# coffee_machine.net
KiCad netlist of a schematic drawn in EAGLE
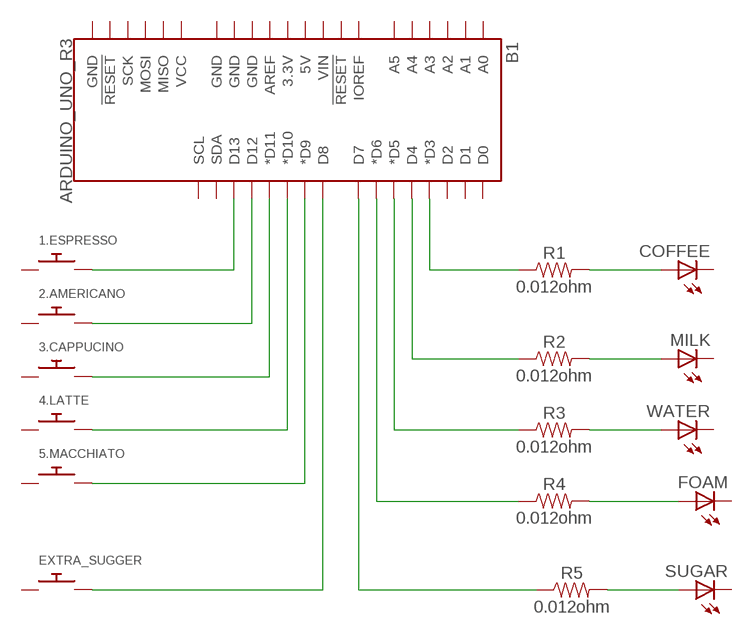
[diagram p0: schematic, sheet 1]

(export (version "E")
  (design (tool "Eeschema 10.0.6"))
  (components
    (comp (ref "1.ESPRESSO")
      (value "SWITCH_PUSHBUTTONEVQ-PE")
      (footprint "eagle-import:TACT_PANA-EVQ")
      (libsource (lib "eagle-import") (part "SWITCH_PUSHBUTTONEVQ-PE"))
    )
    (comp (ref "2.AMERICANO")
      (value "SWITCH_PUSHBUTTONEVQ-PE")
      (footprint "eagle-import:TACT_PANA-EVQ")
      (libsource (lib "eagle-import") (part "SWITCH_PUSHBUTTONEVQ-PE"))
    )
    (comp (ref "3.CAPPUCINO")
      (value "SWITCH_PUSHBUTTONEVQ-PE")
      (footprint "eagle-import:TACT_PANA-EVQ")
      (libsource (lib "eagle-import") (part "SWITCH_PUSHBUTTONEVQ-PE"))
    )
    (comp (ref "4.LATTE")
      (value "SWITCH_PUSHBUTTONEVQ-PE")
      (footprint "eagle-import:TACT_PANA-EVQ")
      (libsource (lib "eagle-import") (part "SWITCH_PUSHBUTTONEVQ-PE"))
    )
    (comp (ref "5.MACCHIATO")
      (value "SWITCH_PUSHBUTTONEVQ-PE")
      (footprint "eagle-import:TACT_PANA-EVQ")
      (libsource (lib "eagle-import") (part "SWITCH_PUSHBUTTONEVQ-PE"))
    )
    (comp (ref "B1")
      (value "ARDUINO_UNO_R3")
      (footprint "eagle-import:ARDUINO_R3")
      (libsource (lib "eagle-import") (part "ARDUINO_UNO_R3"))
    )
    (comp (ref "COFFEE")
      (value "LED3MM")
      (footprint "eagle-import:LED3MM")
      (libsource (lib "eagle-import") (part "LED3MM"))
    )
    (comp (ref "EXTRA_SUGGER")
      (value "SWITCH_PUSHBUTTONEVQ-PE")
      (footprint "eagle-import:TACT_PANA-EVQ")
      (libsource (lib "eagle-import") (part "SWITCH_PUSHBUTTONEVQ-PE"))
    )
    (comp (ref "FOAM")
      (value "LED3MM")
      (footprint "eagle-import:LED3MM")
      (libsource (lib "eagle-import") (part "LED3MM"))
    )
    (comp (ref "MILK")
      (value "LED3MM")
      (footprint "eagle-import:LED3MM")
      (libsource (lib "eagle-import") (part "LED3MM"))
    )
    (comp (ref "R1")
      (value "0.012ohm")
      (footprint "eagle-import:0603")
      (libsource (lib "eagle-import") (part "0.012OHM0603"))
    )
    (comp (ref "R2")
      (value "0.012ohm")
      (footprint "eagle-import:0603")
      (libsource (lib "eagle-import") (part "0.012OHM0603"))
    )
    (comp (ref "R3")
      (value "0.012ohm")
      (footprint "eagle-import:0603")
      (libsource (lib "eagle-import") (part "0.012OHM0603"))
    )
    (comp (ref "R4")
      (value "0.012ohm")
      (footprint "eagle-import:0603")
      (libsource (lib "eagle-import") (part "0.012OHM0603"))
    )
    (comp (ref "R5")
      (value "0.012ohm")
      (footprint "eagle-import:0603")
      (libsource (lib "eagle-import") (part "0.012OHM0603"))
    )
    (comp (ref "SUGAR")
      (value "LED3MM")
      (footprint "eagle-import:LED3MM")
      (libsource (lib "eagle-import") (part "LED3MM"))
    )
    (comp (ref "WATER")
      (value "LED3MM")
      (footprint "eagle-import:LED3MM")
      (libsource (lib "eagle-import") (part "LED3MM"))
    )
  )
  (nets
    (net (code "1") (name "Net-(1.ESPRESSO-PadP$2)") (class "Default")
      (node (ref "1.ESPRESSO") (pin "P$2") (pinfunction "P$2_P$2") (pintype "passive"))
      (node (ref "B1") (pin "D13") (pinfunction "D13_D13") (pintype "bidirectional"))
    )
    (net (code "2") (name "Net-(2.AMERICANO-PadP$2)") (class "Default")
      (node (ref "2.AMERICANO") (pin "P$2") (pinfunction "P$2_P$2") (pintype "passive"))
      (node (ref "B1") (pin "D12") (pinfunction "D12_D12") (pintype "bidirectional"))
    )
    (net (code "3") (name "Net-(B1-*D3)") (class "Default")
      (node (ref "B1") (pin "D3") (pinfunction "*D3_D3") (pintype "bidirectional"))
      (node (ref "R1") (pin "1") (pinfunction "1_1") (pintype "passive"))
    )
    (net (code "4") (name "Net-(B1-*D5)") (class "Default")
      (node (ref "B1") (pin "D5") (pinfunction "*D5_D5") (pintype "bidirectional"))
      (node (ref "R3") (pin "1") (pinfunction "1_1") (pintype "passive"))
    )
    (net (code "5") (name "Net-(B1-*D6)") (class "Default")
      (node (ref "B1") (pin "D6") (pinfunction "*D6_D6") (pintype "bidirectional"))
      (node (ref "R4") (pin "1") (pinfunction "1_1") (pintype "passive"))
    )
    (net (code "6") (name "Net-(B1-*D9)") (class "Default")
      (node (ref "5.MACCHIATO") (pin "P$2") (pinfunction "P$2_P$2") (pintype "passive"))
      (node (ref "B1") (pin "D9") (pinfunction "*D9_D9") (pintype "bidirectional"))
    )
    (net (code "7") (name "Net-(B1-*D10)") (class "Default")
      (node (ref "4.LATTE") (pin "P$2") (pinfunction "P$2_P$2") (pintype "passive"))
      (node (ref "B1") (pin "D10") (pinfunction "*D10_D10") (pintype "bidirectional"))
    )
    (net (code "8") (name "Net-(B1-*D11)") (class "Default")
      (node (ref "3.CAPPUCINO") (pin "P$2") (pinfunction "P$2_P$2") (pintype "passive"))
      (node (ref "B1") (pin "D11") (pinfunction "*D11_D11") (pintype "bidirectional"))
    )
    (net (code "9") (name "Net-(B1-PadD4)") (class "Default")
      (node (ref "B1") (pin "D4") (pinfunction "D4_D4") (pintype "bidirectional"))
      (node (ref "R2") (pin "1") (pinfunction "1_1") (pintype "passive"))
    )
    (net (code "10") (name "Net-(B1-PadD7)") (class "Default")
      (node (ref "B1") (pin "D7") (pinfunction "D7_D7") (pintype "bidirectional"))
      (node (ref "R5") (pin "1") (pinfunction "1_1") (pintype "passive"))
    )
    (net (code "11") (name "Net-(B1-PadD8)") (class "Default")
      (node (ref "B1") (pin "D8") (pinfunction "D8_D8") (pintype "bidirectional"))
      (node (ref "EXTRA_SUGGER") (pin "P$2") (pinfunction "P$2_P$2") (pintype "passive"))
    )
    (net (code "12") (name "Net-(COFFEE-PadA)") (class "Default")
      (node (ref "COFFEE") (pin "A") (pinfunction "A_A") (pintype "passive"))
      (node (ref "R1") (pin "2") (pinfunction "2_2") (pintype "passive"))
    )
    (net (code "13") (name "Net-(FOAM-PadA)") (class "Default")
      (node (ref "FOAM") (pin "A") (pinfunction "A_A") (pintype "passive"))
      (node (ref "R4") (pin "2") (pinfunction "2_2") (pintype "passive"))
    )
    (net (code "14") (name "Net-(MILK-PadA)") (class "Default")
      (node (ref "MILK") (pin "A") (pinfunction "A_A") (pintype "passive"))
      (node (ref "R2") (pin "2") (pinfunction "2_2") (pintype "passive"))
    )
    (net (code "15") (name "Net-(R3-Pad2)") (class "Default")
      (node (ref "R3") (pin "2") (pinfunction "2_2") (pintype "passive"))
      (node (ref "WATER") (pin "A") (pinfunction "A_A") (pintype "passive"))
    )
    (net (code "16") (name "Net-(R5-Pad2)") (class "Default")
      (node (ref "R5") (pin "2") (pinfunction "2_2") (pintype "passive"))
      (node (ref "SUGAR") (pin "A") (pinfunction "A_A") (pintype "passive"))
    )
    (net (code "17") (name "unconnected-(1.ESPRESSO-PadP$1)") (class "Default")
      (node (ref "1.ESPRESSO") (pin "P$1") (pinfunction "P$1_P$1") (pintype "passive"))
    )
    (net (code "18") (name "unconnected-(2.AMERICANO-PadP$1)") (class "Default")
      (node (ref "2.AMERICANO") (pin "P$1") (pinfunction "P$1_P$1") (pintype "passive"))
    )
    (net (code "19") (name "unconnected-(3.CAPPUCINO-PadP$1)") (class "Default")
      (node (ref "3.CAPPUCINO") (pin "P$1") (pinfunction "P$1_P$1") (pintype "passive"))
    )
    (net (code "20") (name "unconnected-(4.LATTE-PadP$1)") (class "Default")
      (node (ref "4.LATTE") (pin "P$1") (pinfunction "P$1_P$1") (pintype "passive"))
    )
    (net (code "21") (name "unconnected-(5.MACCHIATO-PadP$1)") (class "Default")
      (node (ref "5.MACCHIATO") (pin "P$1") (pinfunction "P$1_P$1") (pintype "passive"))
    )
    (net (code "22") (name "unconnected-(B1-GND-PadGND@1)") (class "Default")
      (node (ref "B1") (pin "GND@1") (pinfunction "GND_GND@1") (pintype "bidirectional"))
    )
    (net (code "23") (name "unconnected-(B1-GND-PadGND@2)") (class "Default")
      (node (ref "B1") (pin "GND@2") (pinfunction "GND_GND@2") (pintype "bidirectional"))
    )
    (net (code "24") (name "unconnected-(B1-GND-PadGND@3)") (class "Default")
      (node (ref "B1") (pin "GND@3") (pinfunction "GND_GND@3") (pintype "bidirectional"))
    )
    (net (code "25") (name "unconnected-(B1-GND-PadGND@4)") (class "Default")
      (node (ref "B1") (pin "GND@4") (pinfunction "GND_GND@4") (pintype "bidirectional"))
    )
    (net (code "26") (name "unconnected-(B1-Pad3.3V)") (class "Default")
      (node (ref "B1") (pin "3.3V") (pinfunction "3.3V_3.3V") (pintype "bidirectional"))
    )
    (net (code "27") (name "unconnected-(B1-Pad5V)") (class "Default")
      (node (ref "B1") (pin "5V") (pinfunction "5V_5V") (pintype "bidirectional"))
    )
    (net (code "28") (name "unconnected-(B1-PadA0)") (class "Default")
      (node (ref "B1") (pin "A0") (pinfunction "A0_A0") (pintype "bidirectional"))
    )
    (net (code "29") (name "unconnected-(B1-PadA1)") (class "Default")
      (node (ref "B1") (pin "A1") (pinfunction "A1_A1") (pintype "bidirectional"))
    )
    (net (code "30") (name "unconnected-(B1-PadA2)") (class "Default")
      (node (ref "B1") (pin "A2") (pinfunction "A2_A2") (pintype "bidirectional"))
    )
    (net (code "31") (name "unconnected-(B1-PadA3)") (class "Default")
      (node (ref "B1") (pin "A3") (pinfunction "A3_A3") (pintype "bidirectional"))
    )
    (net (code "32") (name "unconnected-(B1-PadA4)") (class "Default")
      (node (ref "B1") (pin "A4") (pinfunction "A4_A4") (pintype "bidirectional"))
    )
    (net (code "33") (name "unconnected-(B1-PadA5)") (class "Default")
      (node (ref "B1") (pin "A5") (pinfunction "A5_A5") (pintype "bidirectional"))
    )
    (net (code "34") (name "unconnected-(B1-PadAREF)") (class "Default")
      (node (ref "B1") (pin "AREF") (pinfunction "AREF_AREF") (pintype "bidirectional"))
    )
    (net (code "35") (name "unconnected-(B1-PadD0)") (class "Default")
      (node (ref "B1") (pin "D0") (pinfunction "D0_D0") (pintype "bidirectional"))
    )
    (net (code "36") (name "unconnected-(B1-PadD1)") (class "Default")
      (node (ref "B1") (pin "D1") (pinfunction "D1_D1") (pintype "bidirectional"))
    )
    (net (code "37") (name "unconnected-(B1-PadD2)") (class "Default")
      (node (ref "B1") (pin "D2") (pinfunction "D2_D2") (pintype "bidirectional"))
    )
    (net (code "38") (name "unconnected-(B1-PadIOREF)") (class "Default")
      (node (ref "B1") (pin "IOREF") (pinfunction "IOREF_IOREF") (pintype "bidirectional"))
    )
    (net (code "39") (name "unconnected-(B1-PadMISO)") (class "Default")
      (node (ref "B1") (pin "MISO") (pinfunction "MISO_MISO") (pintype "bidirectional"))
    )
    (net (code "40") (name "unconnected-(B1-PadMOSI)") (class "Default")
      (node (ref "B1") (pin "MOSI") (pinfunction "MOSI_MOSI") (pintype "bidirectional"))
    )
    (net (code "41") (name "unconnected-(B1-PadSCK)") (class "Default")
      (node (ref "B1") (pin "SCK") (pinfunction "SCK_SCK") (pintype "bidirectional"))
    )
    (net (code "42") (name "unconnected-(B1-PadSCL)") (class "Default")
      (node (ref "B1") (pin "SCL") (pinfunction "SCL_SCL") (pintype "bidirectional"))
    )
    (net (code "43") (name "unconnected-(B1-PadSDA)") (class "Default")
      (node (ref "B1") (pin "SDA") (pinfunction "SDA_SDA") (pintype "bidirectional"))
    )
    (net (code "44") (name "unconnected-(B1-PadVCC)") (class "Default")
      (node (ref "B1") (pin "VCC") (pinfunction "VCC_VCC") (pintype "bidirectional"))
    )
    (net (code "45") (name "unconnected-(B1-PadVIN)") (class "Default")
      (node (ref "B1") (pin "VIN") (pinfunction "VIN_VIN") (pintype "bidirectional"))
    )
    (net (code "46") (name "unconnected-(B1-~{RESET}-PadRESET@1)") (class "Default")
      (node (ref "B1") (pin "RESET@1") (pinfunction "~{RESET}_RESET@1") (pintype "bidirectional"))
    )
    (net (code "47") (name "unconnected-(B1-~{RESET}-PadRESET@2)") (class "Default")
      (node (ref "B1") (pin "RESET@2") (pinfunction "~{RESET}_RESET@2") (pintype "bidirectional"))
    )
    (net (code "48") (name "unconnected-(COFFEE-C-PadK)") (class "Default")
      (node (ref "COFFEE") (pin "K") (pinfunction "C_K") (pintype "passive"))
    )
    (net (code "49") (name "unconnected-(EXTRA_SUGGER-PadP$1)") (class "Default")
      (node (ref "EXTRA_SUGGER") (pin "P$1") (pinfunction "P$1_P$1") (pintype "passive"))
    )
    (net (code "50") (name "unconnected-(FOAM-C-PadK)") (class "Default")
      (node (ref "FOAM") (pin "K") (pinfunction "C_K") (pintype "passive"))
    )
    (net (code "51") (name "unconnected-(MILK-C-PadK)") (class "Default")
      (node (ref "MILK") (pin "K") (pinfunction "C_K") (pintype "passive"))
    )
    (net (code "52") (name "unconnected-(SUGAR-C-PadK)") (class "Default")
      (node (ref "SUGAR") (pin "K") (pinfunction "C_K") (pintype "passive"))
    )
    (net (code "53") (name "unconnected-(WATER-C-PadK)") (class "Default")
      (node (ref "WATER") (pin "K") (pinfunction "C_K") (pintype "passive"))
    )
  )
)
